# Battery_and_Charging.net
KiCad netlist of a schematic drawn in Altium Designer
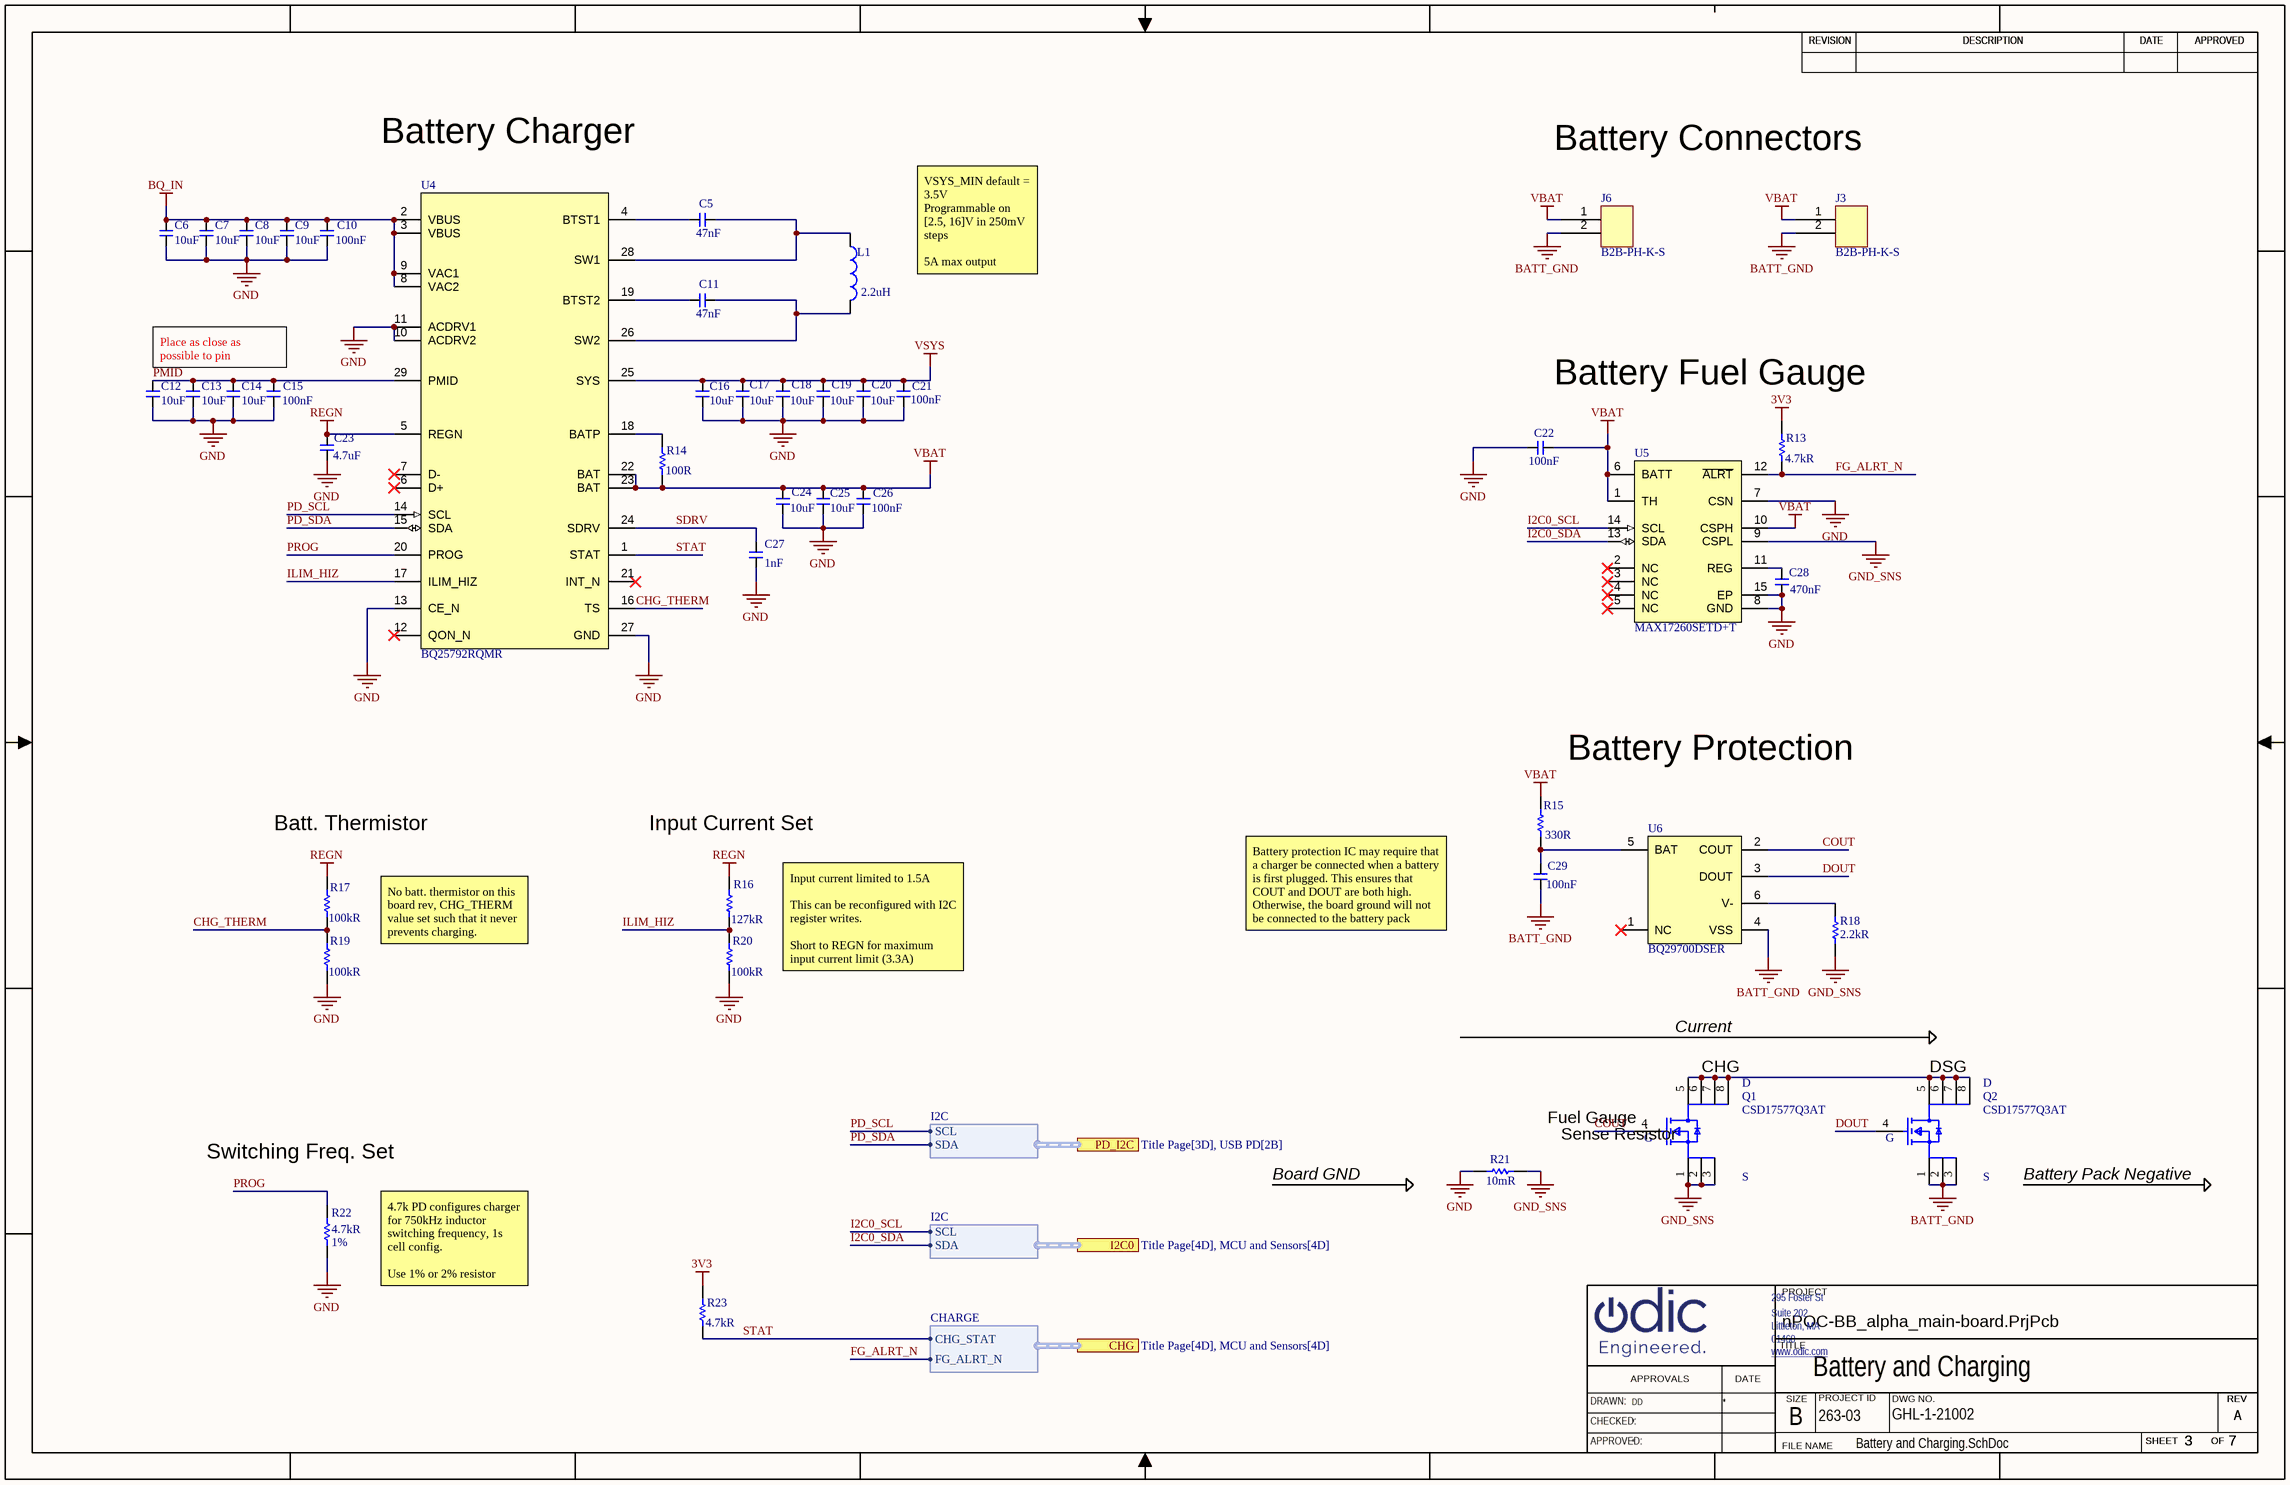
[diagram p0: Battery and Charging.SchDoc]

(export (version "E")
  (design (tool "Eeschema 10.0.6"))
  (components
    (comp (ref "C5")
      (value "C0402_47n_50V_10pct")
      (footprint "C0402")
      (description "CGA2B3X7R1H473K050BB")
      (fields (field (name "TOLERANCE") "10%") (field (name "CAPACITANCE") "47nF"))
      (libsource (lib "Odic Inc") (part "cAP"))
    )
    (comp (ref "C6")
      (value "C0603_10u_25V_10pct")
      (footprint "C0603")
      (description "GRM188R61E106KA73J")
      (fields (field (name "CAPACITANCE") "10uF") (field (name "TOLERANCE") "10%"))
      (libsource (lib "Odic Inc") (part "cAP"))
    )
    (comp (ref "C7")
      (value "C0603_10u_25V_10pct")
      (footprint "C0603")
      (description "GRM188R61E106KA73J")
      (fields (field (name "CAPACITANCE") "10uF") (field (name "TOLERANCE") "10%"))
      (libsource (lib "Odic Inc") (part "cAP"))
    )
    (comp (ref "C8")
      (value "C0603_10u_25V_10pct")
      (footprint "C0603")
      (description "GRM188R61E106KA73J")
      (fields (field (name "CAPACITANCE") "10uF") (field (name "TOLERANCE") "10%"))
      (libsource (lib "Odic Inc") (part "cAP"))
    )
    (comp (ref "C9")
      (value "C0603_10u_25V_10pct")
      (footprint "C0603")
      (description "GRM188R61E106KA73J")
      (fields (field (name "CAPACITANCE") "10uF") (field (name "TOLERANCE") "10%"))
      (libsource (lib "Odic Inc") (part "cAP"))
    )
    (comp (ref "C10")
      (value "C0402_0u1_25V_10pct")
      (footprint "C0402")
      (description "Cap Ceramic 0.1uF 25V X5R 10% Pad SMD 0402 Multi Layer Ceramic Capacitor (MLCC)")
      (fields
        (field (name "VOLTAGE") "25V")
        (field (name "TOLERANCE") "10%")
        (field (name "CAPACITANCE") "100nF")
      )
      (libsource (lib "Odic Inc") (part "cAP"))
    )
    (comp (ref "C11")
      (value "C0402_47n_50V_10pct")
      (footprint "C0402")
      (description "CGA2B3X7R1H473K050BB")
      (fields (field (name "TOLERANCE") "10%") (field (name "CAPACITANCE") "47nF"))
      (libsource (lib "Odic Inc") (part "cAP"))
    )
    (comp (ref "C12")
      (value "C0603_10u_25V_10pct")
      (footprint "C0603")
      (description "GRM188R61E106KA73J")
      (fields (field (name "CAPACITANCE") "10uF") (field (name "TOLERANCE") "10%"))
      (libsource (lib "Odic Inc") (part "cAP"))
    )
    (comp (ref "C13")
      (value "C0603_10u_25V_10pct")
      (footprint "C0603")
      (description "GRM188R61E106KA73J")
      (fields (field (name "CAPACITANCE") "10uF") (field (name "TOLERANCE") "10%"))
      (libsource (lib "Odic Inc") (part "cAP"))
    )
    (comp (ref "C14")
      (value "C0603_10u_25V_10pct")
      (footprint "C0603")
      (description "GRM188R61E106KA73J")
      (fields (field (name "CAPACITANCE") "10uF") (field (name "TOLERANCE") "10%"))
      (libsource (lib "Odic Inc") (part "cAP"))
    )
    (comp (ref "C15")
      (value "C0402_0u1_25V_10pct")
      (footprint "C0402")
      (description "Cap Ceramic 0.1uF 25V X5R 10% Pad SMD 0402 Multi Layer Ceramic Capacitor (MLCC)")
      (fields
        (field (name "VOLTAGE") "25V")
        (field (name "TOLERANCE") "10%")
        (field (name "CAPACITANCE") "100nF")
      )
      (libsource (lib "Odic Inc") (part "cAP"))
    )
    (comp (ref "C16")
      (value "C0603_10u_25V_10pct")
      (footprint "C0603")
      (description "GRM188R61E106KA73J")
      (fields (field (name "CAPACITANCE") "10uF") (field (name "TOLERANCE") "10%"))
      (libsource (lib "Odic Inc") (part "cAP"))
    )
    (comp (ref "C17")
      (value "C0603_10u_25V_10pct")
      (footprint "C0603")
      (description "GRM188R61E106KA73J")
      (fields (field (name "CAPACITANCE") "10uF") (field (name "TOLERANCE") "10%"))
      (libsource (lib "Odic Inc") (part "cAP"))
    )
    (comp (ref "C18")
      (value "C0603_10u_25V_10pct")
      (footprint "C0603")
      (description "GRM188R61E106KA73J")
      (fields (field (name "CAPACITANCE") "10uF") (field (name "TOLERANCE") "10%"))
      (libsource (lib "Odic Inc") (part "cAP"))
    )
    (comp (ref "C19")
      (value "C0603_10u_25V_10pct")
      (footprint "C0603")
      (description "GRM188R61E106KA73J")
      (fields (field (name "CAPACITANCE") "10uF") (field (name "TOLERANCE") "10%"))
      (libsource (lib "Odic Inc") (part "cAP"))
    )
    (comp (ref "C20")
      (value "C0603_10u_25V_10pct")
      (footprint "C0603")
      (description "GRM188R61E106KA73J")
      (fields (field (name "CAPACITANCE") "10uF") (field (name "TOLERANCE") "10%"))
      (libsource (lib "Odic Inc") (part "cAP"))
    )
    (comp (ref "C21")
      (value "C0402_0u1_25V_10pct")
      (footprint "C0402")
      (description "Cap Ceramic 0.1uF 25V X5R 10% Pad SMD 0402 Multi Layer Ceramic Capacitor (MLCC)")
      (fields
        (field (name "VOLTAGE") "25V")
        (field (name "TOLERANCE") "10%")
        (field (name "CAPACITANCE") "100nF")
      )
      (libsource (lib "Odic Inc") (part "cAP"))
    )
    (comp (ref "C22")
      (value "C0402_100n_16V_10pct")
      (footprint "C0402")
      (description "0.1 µF ±10% 16V Ceramic Capacitor X7R 0402 (1005 Metric)")
      (fields
        (field (name "VOLTAGE") "16V")
        (field (name "TOLERANCE") "10%")
        (field (name "CAPACITANCE") "100nF")
      )
      (libsource (lib "Odic Inc") (part "cAP"))
    )
    (comp (ref "C23")
      (value "C0402_4u7_10V_20pct")
      (footprint "C0402")
      (description "Cap Ceramic 4.7uF 10V X5R 20% SMD 0402 85°C Paper T/R")
      (fields (field (name "CAPACITANCE") "4.7uF") (field (name "TOLERANCE") "20%"))
      (libsource (lib "Odic Inc") (part "cAP"))
    )
    (comp (ref "C24")
      (value "C0603_10u_25V_10pct")
      (footprint "C0603")
      (description "GRM188R61E106KA73J")
      (fields (field (name "CAPACITANCE") "10uF") (field (name "TOLERANCE") "10%"))
      (libsource (lib "Odic Inc") (part "cAP"))
    )
    (comp (ref "C25")
      (value "C0603_10u_25V_10pct")
      (footprint "C0603")
      (description "GRM188R61E106KA73J")
      (fields (field (name "CAPACITANCE") "10uF") (field (name "TOLERANCE") "10%"))
      (libsource (lib "Odic Inc") (part "cAP"))
    )
    (comp (ref "C26")
      (value "C0402_0u1_25V_10pct")
      (footprint "C0402")
      (description "Cap Ceramic 0.1uF 25V X5R 10% Pad SMD 0402 Multi Layer Ceramic Capacitor (MLCC)")
      (fields
        (field (name "VOLTAGE") "25V")
        (field (name "TOLERANCE") "10%")
        (field (name "CAPACITANCE") "100nF")
      )
      (libsource (lib "Odic Inc") (part "cAP"))
    )
    (comp (ref "C27")
      (value "C0402_1n_50V_10pct")
      (footprint "C0402")
      (description "0402 1 nF 50V ±10 % Tolerance X7R Surface Mount Multilayer Ceramic Capacitor")
      (fields
        (field (name "TOLERANCE") "10%")
        (field (name "VOLTAGE") "50V")
        (field (name "CAPACITANCE") "1nF")
      )
      (libsource (lib "Odic Inc") (part "cAP"))
    )
    (comp (ref "C28")
      (value "C0402_470n_6V3_10pct")
      (footprint "C0402")
      (description "Ceramic capacitor SMD-0402 470nF /6, 3V X5R# K +-10%, Samsung, RoHS")
      (fields
        (field (name "CAPACITANCE") "470nF")
        (field (name "VOLTAGE") "6.3V")
        (field (name "TOLERANCE") "10%")
      )
      (libsource (lib "Odic Inc") (part "cAP"))
    )
    (comp (ref "C29")
      (value "C0402_100n_16V_10pct")
      (footprint "C0402")
      (description "0.1 µF ±10% 16V Ceramic Capacitor X7R 0402 (1005 Metric)")
      (fields
        (field (name "VOLTAGE") "16V")
        (field (name "TOLERANCE") "10%")
        (field (name "CAPACITANCE") "100nF")
      )
      (libsource (lib "Odic Inc") (part "cAP"))
    )
    (comp (ref "J3")
      (value "B2B-PH-K-S")
      (footprint "JST_B2B-PH-K-S")
      (description "Connector Header, PH Series, 2 Position, 2.00mm, Through Hole, Press-Fit, Solder, Natural")
      (libsource (lib "Odic Inc") (part "B2BPHKSLFSN-Symbol-1"))
    )
    (comp (ref "J6")
      (value "B2B-PH-K-S")
      (footprint "JST_B2B-PH-K-S")
      (description "Connector Header, PH Series, 2 Position, 2.00mm, Through Hole, Press-Fit, Solder, Natural")
      (libsource (lib "Odic Inc") (part "B2BPHKSLFSN-Symbol-1"))
    )
    (comp (ref "L1")
      (value "2.2uH")
      (footprint "ind2_5p4x5p2mm")
      (description "FIXED IND 2.2UH 5.8A 29 MOHM")
      (fields (field (name "TOLERANCE") "20%") (field (name "Comment") "0530CDMCCDS-2R2MC"))
      (libsource (lib "Odic Inc") (part "IND"))
    )
    (comp (ref "Q1")
      (value "CSD17577Q3AT")
      (footprint "dfn8_3p1x3p25_p65mm")
      (description "30-V, N channel NexFET™ power MOSFET, single SON 3 mm x 3 mm, 6.4 mOhm 8-VSONP -55 to 150")
      (libsource (lib "Odic Inc") (part "e0baf4780622716b99a4fe4ad34e686"))
    )
    (comp (ref "Q2")
      (value "CSD17577Q3AT")
      (footprint "dfn8_3p1x3p25_p65mm")
      (description "30-V, N channel NexFET™ power MOSFET, single SON 3 mm x 3 mm, 6.4 mOhm 8-VSONP -55 to 150")
      (libsource (lib "Odic Inc") (part "e0baf4780622716b99a4fe4ad34e686"))
    )
    (comp (ref "R13")
      (value "R0402_4k7_1pct")
      (footprint "R0402")
      (description "RES 4.7K OHM 1% 1/16W 0402")
      (fields (field (name "TOLERANCE") "1%") (field (name "RESISTANCE") "4.7kR"))
      (libsource (lib "Odic Inc") (part "RES"))
    )
    (comp (ref "R14")
      (value "100R")
      (footprint "R0402")
      (description "Res General Purpose Thick Film 0402 100 Ohm 1% 1/16W ±200ppm/°C Molded SMD Paper T/R")
      (fields (field (name "TOLERANCE") "1%") (field (name "Comment") "R0402_100R_1pct"))
      (libsource (lib "Odic Inc") (part "RES"))
    )
    (comp (ref "R15")
      (value "330R")
      (footprint "R0402")
      (description "SMD Chip Resistor, 330 Ohm, ± 1%, 63 mW, 0402 [1005 Metric], Thick Film, General Purpose")
      (fields (field (name "TOLERANCE") "1%") (field (name "Comment") "R0402_300R_1pct"))
      (libsource (lib "Odic Inc") (part "RES"))
    )
    (comp (ref "R16")
      (value "127kR")
      (footprint "R0402")
      (description "SMD Chip Resistor, 127 kOhm, ± 1%, 63 mW, 0402 [1005 Metric], Thick Film, General Purpose")
      (fields (field (name "TOLERANCE") "1%") (field (name "Comment") "R0402_127k_1pct"))
      (libsource (lib "Odic Inc") (part "RES"))
    )
    (comp (ref "R17")
      (value "R0402_100k_1pct")
      (footprint "R0402")
      (description "Res General Purpose Thick Film 0402 100K Ohm 1% 1/16W ±100ppm/°C Molded SMD Paper T/R")
      (fields (field (name "RESISTANCE") "100kR") (field (name "TOLERANCE") "1%"))
      (libsource (lib "Odic Inc") (part "RES"))
    )
    (comp (ref "R18")
      (value "R0402_2k2_5pct")
      (footprint "R0402")
      (description "Res Thick Film 0402 2.2K Ohm 5% 1/10W +/-200ppm/ßC Molded SMD Punched Carrier T/R")
      (fields (field (name "TOLERANCE") "5%") (field (name "RESISTANCE") "2.2kR"))
      (libsource (lib "Odic Inc") (part "RES"))
    )
    (comp (ref "R19")
      (value "R0402_100k_1pct")
      (footprint "R0402")
      (description "Res General Purpose Thick Film 0402 100K Ohm 1% 1/16W ±100ppm/°C Molded SMD Paper T/R")
      (fields (field (name "RESISTANCE") "100kR") (field (name "TOLERANCE") "1%"))
      (libsource (lib "Odic Inc") (part "RES"))
    )
    (comp (ref "R20")
      (value "R0402_100k_1pct")
      (footprint "R0402")
      (description "Res General Purpose Thick Film 0402 100K Ohm 1% 1/16W ±100ppm/°C Molded SMD Paper T/R")
      (fields (field (name "RESISTANCE") "100kR") (field (name "TOLERANCE") "1%"))
      (libsource (lib "Odic Inc") (part "RES"))
    )
    (comp (ref "R21")
      (value "10mR")
      (footprint "R0603")
      (description "SMD Chip Resistor, 10 Milliohm, ± 1%, 250 mW, 0603 [1608 Metric], Thick Film, High Power")
      (fields (field (name "TOLERANCE") "1%") (field (name "Comment") "R0603_0R01_1pct"))
      (libsource (lib "Odic Inc") (part "RES"))
    )
    (comp (ref "R22")
      (value "R0402_4k7_1pct")
      (footprint "R0402")
      (description "RES 4.7K OHM 1% 1/16W 0402")
      (fields
        (field (name "TOLERANCE") "1%")
        (field (name "RESISTANCE TOLERANCE") "1%")
        (field (name "RESISTANCE") "4.7kR")
      )
      (libsource (lib "Odic Inc") (part "RES"))
    )
    (comp (ref "R23")
      (value "R0402_4k7_1pct")
      (footprint "R0402")
      (description "RES 4.7K OHM 1% 1/16W 0402")
      (fields (field (name "TOLERANCE") "1%") (field (name "RESISTANCE") "4.7kR"))
      (libsource (lib "Odic Inc") (part "RES"))
    )
    (comp (ref "U4")
      (value "BQ25792RQMR")
      (footprint "qfn29_4x4_p4mm-RQM0029A")
      (description "I2C Controlled, 1-4 Cell, 5-A Buck-Boost Battery Charger with Dual-Input")
      (libsource (lib "Odic Inc") (part "PQ25792RQMR"))
    )
    (comp (ref "U5")
      (value "MAX17260SETD+T")
      (footprint "dfn14_3x3_p4mm")
      (description "Battery Management 5.1 A 1-Cell Fuel Gauge with ModelGauge m5 EZ and Optional H")
      (libsource (lib "Odic Inc") (part "MAX17260SETD+T -- Symbol"))
    )
    (comp (ref "U6")
      (value "BQ29700DSER")
      (footprint "dfn6_1p5x1p5_p5mm")
      (description "Li-Ion/Li Polymer Advanced Single-Cell Battery Protector IC Family 6-WSON -40 to 85")
      (libsource (lib "Odic Inc") (part "cb1a035e2e9bf15fad579f9d3aca51e"))
    )
  )
  (nets
    (net (code "3") (name "/CHG_THERM") (class "Default")
      (node (ref "R17") (pin "1") (pinfunction "1_1") (pintype "passive"))
      (node (ref "R19") (pin "2") (pinfunction "2_2") (pintype "passive"))
      (node (ref "U4") (pin "16") (pinfunction "TS_16") (pintype "passive"))
    )
    (net (code "4") (name "/COUT") (class "Default")
      (node (ref "Q1") (pin "4") (pinfunction "G_4") (pintype "passive"))
      (node (ref "U6") (pin "2") (pinfunction "COUT_2") (pintype "passive"))
    )
    (net (code "5") (name "/DOUT") (class "Default")
      (node (ref "Q2") (pin "4") (pinfunction "G_4") (pintype "passive"))
      (node (ref "U6") (pin "3") (pinfunction "DOUT_3") (pintype "passive"))
    )
    (net (code "6") (name "/FG_ALRT_N") (class "Default")
      (node (ref "R13") (pin "1") (pinfunction "1_1") (pintype "passive"))
      (node (ref "U5") (pin "12") (pinfunction "~{ALRT}_12") (pintype "open_collector"))
    )
    (net (code "7") (name "/I2C0_SCL") (class "Default")
      (node (ref "U5") (pin "14") (pinfunction "SCL_14") (pintype "input"))
    )
    (net (code "8") (name "/I2C0_SDA") (class "Default")
      (node (ref "U5") (pin "13") (pinfunction "SDA_13") (pintype "bidirectional"))
    )
    (net (code "9") (name "/ILIM_HIZ") (class "Default")
      (node (ref "R16") (pin "1") (pinfunction "1_1") (pintype "passive"))
      (node (ref "R20") (pin "2") (pinfunction "2_2") (pintype "passive"))
      (node (ref "U4") (pin "17") (pinfunction "ILIM_HIZ_17") (pintype "passive"))
    )
    (net (code "10") (name "/PD_SCL") (class "Default")
      (node (ref "U4") (pin "14") (pinfunction "SCL_14") (pintype "input"))
    )
    (net (code "11") (name "/PD_SDA") (class "Default")
      (node (ref "U4") (pin "15") (pinfunction "SDA_15") (pintype "bidirectional"))
    )
    (net (code "12") (name "/PMID") (class "Default")
      (node (ref "C12") (pin "2") (pinfunction "2_2") (pintype "passive"))
      (node (ref "C13") (pin "2") (pinfunction "2_2") (pintype "passive"))
      (node (ref "C14") (pin "2") (pinfunction "2_2") (pintype "passive"))
      (node (ref "C15") (pin "2") (pinfunction "2_2") (pintype "passive"))
      (node (ref "U4") (pin "29") (pinfunction "PMID_29") (pintype "passive"))
    )
    (net (code "13") (name "/PROG") (class "Default")
      (node (ref "R22") (pin "2") (pinfunction "2_2") (pintype "passive"))
      (node (ref "U4") (pin "20") (pinfunction "PROG_20") (pintype "passive"))
    )
    (net (code "14") (name "/SDRV") (class "Default")
      (node (ref "C27") (pin "2") (pinfunction "2_2") (pintype "passive"))
      (node (ref "U4") (pin "24") (pinfunction "SDRV_24") (pintype "passive"))
    )
    (net (code "15") (name "/STAT") (class "Default")
      (node (ref "R23") (pin "1") (pinfunction "1_1") (pintype "passive"))
      (node (ref "U4") (pin "1") (pinfunction "STAT_1") (pintype "passive"))
    )
    (net (code "18") (name "3V3") (class "Default")
      (node (ref "R13") (pin "2") (pinfunction "2_2") (pintype "passive"))
      (node (ref "R23") (pin "2") (pinfunction "2_2") (pintype "passive"))
    )
    (net (code "19") (name "BATT_GND") (class "Default")
      (node (ref "C29") (pin "1") (pinfunction "1_1") (pintype "passive"))
      (node (ref "J3") (pin "2") (pinfunction "2_2") (pintype "passive"))
      (node (ref "J6") (pin "2") (pinfunction "2_2") (pintype "passive"))
      (node (ref "Q2") (pin "1") (pinfunction "S_1") (pintype "passive"))
      (node (ref "Q2") (pin "2") (pinfunction "S_2") (pintype "passive"))
      (node (ref "Q2") (pin "3") (pinfunction "S_3") (pintype "passive"))
      (node (ref "U6") (pin "4") (pinfunction "VSS_4") (pintype "power_in"))
    )
    (net (code "20") (name "BQ_IN") (class "Default")
      (node (ref "C10") (pin "2") (pinfunction "2_2") (pintype "passive"))
      (node (ref "C6") (pin "2") (pinfunction "2_2") (pintype "passive"))
      (node (ref "C7") (pin "2") (pinfunction "2_2") (pintype "passive"))
      (node (ref "C8") (pin "2") (pinfunction "2_2") (pintype "passive"))
      (node (ref "C9") (pin "2") (pinfunction "2_2") (pintype "passive"))
      (node (ref "U4") (pin "2") (pinfunction "VBUS_2") (pintype "power_in"))
      (node (ref "U4") (pin "3") (pinfunction "VBUS_3") (pintype "power_in"))
      (node (ref "U4") (pin "8") (pinfunction "VAC2_8") (pintype "power_in"))
      (node (ref "U4") (pin "9") (pinfunction "VAC1_9") (pintype "power_in"))
    )
    (net (code "21") (name "GND") (class "Default")
      (node (ref "C10") (pin "1") (pinfunction "1_1") (pintype "passive"))
      (node (ref "C12") (pin "1") (pinfunction "1_1") (pintype "passive"))
      (node (ref "C13") (pin "1") (pinfunction "1_1") (pintype "passive"))
      (node (ref "C14") (pin "1") (pinfunction "1_1") (pintype "passive"))
      (node (ref "C15") (pin "1") (pinfunction "1_1") (pintype "passive"))
      (node (ref "C16") (pin "1") (pinfunction "1_1") (pintype "passive"))
      (node (ref "C17") (pin "1") (pinfunction "1_1") (pintype "passive"))
      (node (ref "C18") (pin "1") (pinfunction "1_1") (pintype "passive"))
      (node (ref "C19") (pin "1") (pinfunction "1_1") (pintype "passive"))
      (node (ref "C20") (pin "1") (pinfunction "1_1") (pintype "passive"))
      (node (ref "C21") (pin "1") (pinfunction "1_1") (pintype "passive"))
      (node (ref "C22") (pin "2") (pinfunction "2_2") (pintype "passive"))
      (node (ref "C23") (pin "1") (pinfunction "1_1") (pintype "passive"))
      (node (ref "C24") (pin "1") (pinfunction "1_1") (pintype "passive"))
      (node (ref "C25") (pin "1") (pinfunction "1_1") (pintype "passive"))
      (node (ref "C26") (pin "1") (pinfunction "1_1") (pintype "passive"))
      (node (ref "C27") (pin "1") (pinfunction "1_1") (pintype "passive"))
      (node (ref "C28") (pin "1") (pinfunction "1_1") (pintype "passive"))
      (node (ref "C6") (pin "1") (pinfunction "1_1") (pintype "passive"))
      (node (ref "C7") (pin "1") (pinfunction "1_1") (pintype "passive"))
      (node (ref "C8") (pin "1") (pinfunction "1_1") (pintype "passive"))
      (node (ref "C9") (pin "1") (pinfunction "1_1") (pintype "passive"))
      (node (ref "R19") (pin "1") (pinfunction "1_1") (pintype "passive"))
      (node (ref "R20") (pin "1") (pinfunction "1_1") (pintype "passive"))
      (node (ref "R21") (pin "1") (pinfunction "1_1") (pintype "passive"))
      (node (ref "R22") (pin "1") (pinfunction "1_1") (pintype "passive"))
      (node (ref "U4") (pin "10") (pinfunction "ACDRV2_10") (pintype "power_in"))
      (node (ref "U4") (pin "11") (pinfunction "ACDRV1_11") (pintype "power_in"))
      (node (ref "U4") (pin "13") (pinfunction "CE_N_13") (pintype "passive"))
      (node (ref "U4") (pin "27") (pinfunction "GND_27") (pintype "power_in"))
      (node (ref "U5") (pin "15") (pinfunction "EP_15") (pintype "power_in"))
      (node (ref "U5") (pin "7") (pinfunction "CSN_7") (pintype "passive"))
      (node (ref "U5") (pin "8") (pinfunction "GND_8") (pintype "power_in"))
    )
    (net (code "22") (name "GND_SNS") (class "Default")
      (node (ref "Q1") (pin "1") (pinfunction "S_1") (pintype "passive"))
      (node (ref "Q1") (pin "2") (pinfunction "S_2") (pintype "passive"))
      (node (ref "Q1") (pin "3") (pinfunction "S_3") (pintype "passive"))
      (node (ref "R18") (pin "2") (pinfunction "2_2") (pintype "passive"))
      (node (ref "R21") (pin "2") (pinfunction "2_2") (pintype "passive"))
      (node (ref "U5") (pin "9") (pinfunction "CSPL_9") (pintype "passive"))
    )
    (net (code "23") (name "Net-(Q1-D-Pad5)") (class "Default")
      (node (ref "Q1") (pin "5") (pinfunction "D_5") (pintype "passive"))
      (node (ref "Q1") (pin "6") (pinfunction "D_6") (pintype "passive"))
      (node (ref "Q1") (pin "7") (pinfunction "D_7") (pintype "passive"))
      (node (ref "Q1") (pin "8") (pinfunction "D_8") (pintype "passive"))
      (node (ref "Q2") (pin "5") (pinfunction "D_5") (pintype "passive"))
      (node (ref "Q2") (pin "6") (pinfunction "D_6") (pintype "passive"))
      (node (ref "Q2") (pin "7") (pinfunction "D_7") (pintype "passive"))
      (node (ref "Q2") (pin "8") (pinfunction "D_8") (pintype "passive"))
    )
    (net (code "24") (name "Net-(U4-BATP)") (class "Default")
      (node (ref "R14") (pin "2") (pinfunction "2_2") (pintype "passive"))
      (node (ref "U4") (pin "18") (pinfunction "BATP_18") (pintype "passive"))
    )
    (net (code "25") (name "Net-(U4-BTST1)") (class "Default")
      (node (ref "C5") (pin "2") (pinfunction "2_2") (pintype "passive"))
      (node (ref "U4") (pin "4") (pinfunction "BTST1_4") (pintype "passive"))
    )
    (net (code "26") (name "Net-(U4-BTST2)") (class "Default")
      (node (ref "C11") (pin "2") (pinfunction "2_2") (pintype "passive"))
      (node (ref "U4") (pin "19") (pinfunction "BTST2_19") (pintype "passive"))
    )
    (net (code "27") (name "Net-(U4-SW1)") (class "Default")
      (node (ref "C5") (pin "1") (pinfunction "1_1") (pintype "passive"))
      (node (ref "L1") (pin "1") (pinfunction "1_1") (pintype "passive"))
      (node (ref "U4") (pin "28") (pinfunction "SW1_28") (pintype "passive"))
    )
    (net (code "28") (name "Net-(U4-SW2)") (class "Default")
      (node (ref "C11") (pin "1") (pinfunction "1_1") (pintype "passive"))
      (node (ref "L1") (pin "2") (pinfunction "2_2") (pintype "passive"))
      (node (ref "U4") (pin "26") (pinfunction "SW2_26") (pintype "passive"))
    )
    (net (code "29") (name "Net-(U5-REG)") (class "Default")
      (node (ref "C28") (pin "2") (pinfunction "2_2") (pintype "passive"))
      (node (ref "U5") (pin "11") (pinfunction "REG_11") (pintype "power_in"))
    )
    (net (code "30") (name "Net-(U6-BAT)") (class "Default")
      (node (ref "C29") (pin "2") (pinfunction "2_2") (pintype "passive"))
      (node (ref "R15") (pin "1") (pinfunction "1_1") (pintype "passive"))
      (node (ref "U6") (pin "5") (pinfunction "BAT_5") (pintype "power_in"))
    )
    (net (code "31") (name "Net-(U6-V-)") (class "Default")
      (node (ref "R18") (pin "1") (pinfunction "1_1") (pintype "passive"))
      (node (ref "U6") (pin "6") (pinfunction "V-_6") (pintype "passive"))
    )
    (net (code "32") (name "REGN") (class "Default")
      (node (ref "C23") (pin "2") (pinfunction "2_2") (pintype "passive"))
      (node (ref "R16") (pin "2") (pinfunction "2_2") (pintype "passive"))
      (node (ref "R17") (pin "2") (pinfunction "2_2") (pintype "passive"))
      (node (ref "U4") (pin "5") (pinfunction "REGN_5") (pintype "passive"))
    )
    (net (code "33") (name "VBAT") (class "Default")
      (node (ref "C22") (pin "1") (pinfunction "1_1") (pintype "passive"))
      (node (ref "C24") (pin "2") (pinfunction "2_2") (pintype "passive"))
      (node (ref "C25") (pin "2") (pinfunction "2_2") (pintype "passive"))
      (node (ref "C26") (pin "2") (pinfunction "2_2") (pintype "passive"))
      (node (ref "J3") (pin "1") (pinfunction "1_1") (pintype "passive"))
      (node (ref "J6") (pin "1") (pinfunction "1_1") (pintype "passive"))
      (node (ref "R14") (pin "1") (pinfunction "1_1") (pintype "passive"))
      (node (ref "R15") (pin "2") (pinfunction "2_2") (pintype "passive"))
      (node (ref "U4") (pin "22") (pinfunction "BAT_22") (pintype "passive"))
      (node (ref "U4") (pin "23") (pinfunction "BAT_23") (pintype "passive"))
      (node (ref "U5") (pin "1") (pinfunction "TH_1") (pintype "passive"))
      (node (ref "U5") (pin "10") (pinfunction "CSPH_10") (pintype "passive"))
      (node (ref "U5") (pin "6") (pinfunction "BATT_6") (pintype "power_in"))
    )
    (net (code "34") (name "VSYS") (class "Default")
      (node (ref "C16") (pin "2") (pinfunction "2_2") (pintype "passive"))
      (node (ref "C17") (pin "2") (pinfunction "2_2") (pintype "passive"))
      (node (ref "C18") (pin "2") (pinfunction "2_2") (pintype "passive"))
      (node (ref "C19") (pin "2") (pinfunction "2_2") (pintype "passive"))
      (node (ref "C20") (pin "2") (pinfunction "2_2") (pintype "passive"))
      (node (ref "C21") (pin "2") (pinfunction "2_2") (pintype "passive"))
      (node (ref "U4") (pin "25") (pinfunction "SYS_25") (pintype "passive"))
    )
    (net (code "35") (name "unconnected-(U4-D+-Pad6)") (class "Default")
      (node (ref "U4") (pin "6") (pinfunction "D+_6") (pintype "passive+no_connect"))
    )
    (net (code "36") (name "unconnected-(U4-D--Pad7)") (class "Default")
      (node (ref "U4") (pin "7") (pinfunction "D-_7") (pintype "passive+no_connect"))
    )
    (net (code "37") (name "unconnected-(U4-INT_N-Pad21)") (class "Default")
      (node (ref "U4") (pin "21") (pinfunction "INT_N_21") (pintype "passive+no_connect"))
    )
    (net (code "38") (name "unconnected-(U4-QON_N-Pad12)") (class "Default")
      (node (ref "U4") (pin "12") (pinfunction "QON_N_12") (pintype "passive+no_connect"))
    )
    (net (code "39") (name "unconnected-(U5-NC-Pad2)") (class "Default")
      (node (ref "U5") (pin "2") (pinfunction "NC_2") (pintype "passive+no_connect"))
    )
    (net (code "40") (name "unconnected-(U5-NC-Pad3)") (class "Default")
      (node (ref "U5") (pin "3") (pinfunction "NC_3") (pintype "passive+no_connect"))
    )
    (net (code "41") (name "unconnected-(U5-NC-Pad4)") (class "Default")
      (node (ref "U5") (pin "4") (pinfunction "NC_4") (pintype "passive+no_connect"))
    )
    (net (code "42") (name "unconnected-(U5-NC-Pad5)") (class "Default")
      (node (ref "U5") (pin "5") (pinfunction "NC_5") (pintype "passive+no_connect"))
    )
    (net (code "43") (name "unconnected-(U6-NC-Pad1)") (class "Default")
      (node (ref "U6") (pin "1") (pinfunction "NC_1") (pintype "passive+no_connect"))
    )
  )
)
